# PLL.net
KiCad netlist of a schematic drawn in Altium Designer
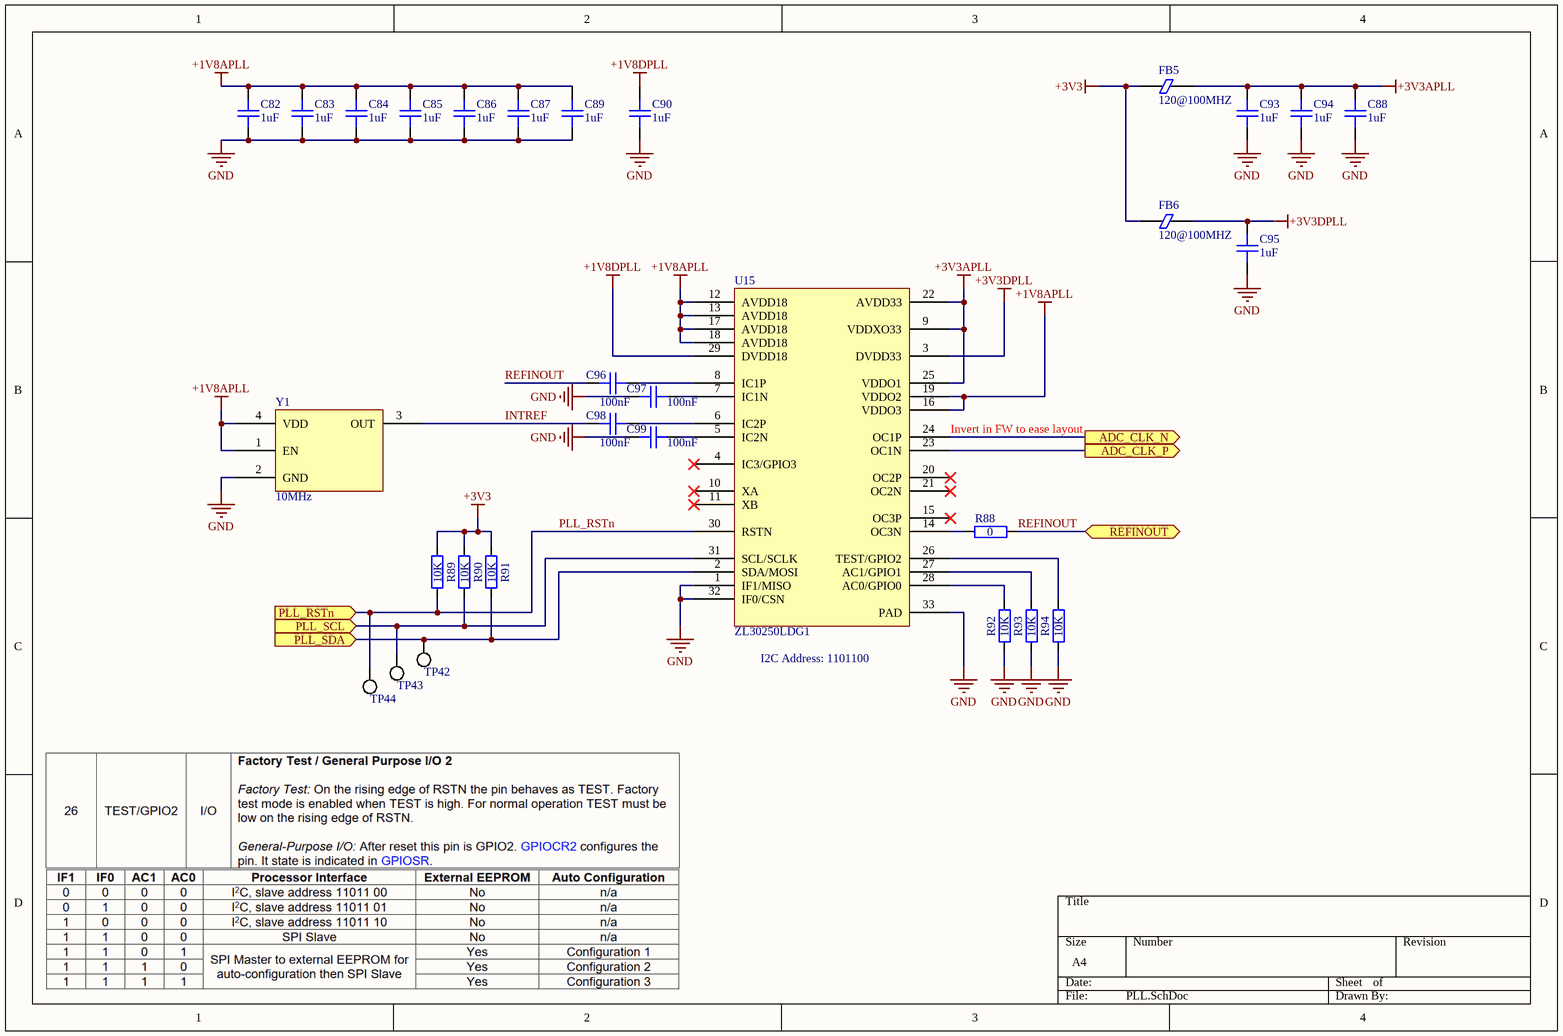
[diagram p0: PLL.SchDoc]

(export (version "E")
  (design (tool "Eeschema 10.0.6"))
  (components
    (comp (ref "C82")
      (value "1uF")
      (footprint "GEN_C_0402")
      (libsource (lib "DSO") (part "CAP 1uF 25V X5R 0402"))
    )
    (comp (ref "C83")
      (value "1uF")
      (footprint "GEN_C_0402")
      (libsource (lib "DSO") (part "CAP 1uF 25V X5R 0402"))
    )
    (comp (ref "C84")
      (value "1uF")
      (footprint "GEN_C_0402")
      (libsource (lib "DSO") (part "CAP 1uF 25V X5R 0402"))
    )
    (comp (ref "C85")
      (value "1uF")
      (footprint "GEN_C_0402")
      (libsource (lib "DSO") (part "CAP 1uF 25V X5R 0402"))
    )
    (comp (ref "C86")
      (value "1uF")
      (footprint "GEN_C_0402")
      (libsource (lib "DSO") (part "CAP 1uF 25V X5R 0402"))
    )
    (comp (ref "C87")
      (value "1uF")
      (footprint "GEN_C_0402")
      (libsource (lib "DSO") (part "CAP 1uF 25V X5R 0402"))
    )
    (comp (ref "C88")
      (value "1uF")
      (footprint "GEN_C_0402")
      (libsource (lib "DSO") (part "CAP 1uF 25V X5R 0402"))
    )
    (comp (ref "C89")
      (value "1uF")
      (footprint "GEN_C_0402")
      (libsource (lib "DSO") (part "CAP 1uF 25V X5R 0402"))
    )
    (comp (ref "C90")
      (value "1uF")
      (footprint "GEN_C_0402")
      (libsource (lib "DSO") (part "CAP 1uF 25V X5R 0402"))
    )
    (comp (ref "C93")
      (value "1uF")
      (footprint "GEN_C_0402")
      (libsource (lib "DSO") (part "CAP 1uF 25V X5R 0402"))
    )
    (comp (ref "C94")
      (value "1uF")
      (footprint "GEN_C_0402")
      (libsource (lib "DSO") (part "CAP 1uF 25V X5R 0402"))
    )
    (comp (ref "C95")
      (value "1uF")
      (footprint "GEN_C_0402")
      (libsource (lib "DSO") (part "CAP 1uF 25V X5R 0402"))
    )
    (comp (ref "C96")
      (value "100nF")
      (footprint "GEN_C_0402")
      (libsource (lib "DSO") (part "CAP 100nF 16V X7R 0402"))
    )
    (comp (ref "C97")
      (value "100nF")
      (footprint "GEN_C_0402")
      (libsource (lib "DSO") (part "CAP 100nF 16V X7R 0402"))
    )
    (comp (ref "C98")
      (value "100nF")
      (footprint "GEN_C_0402")
      (libsource (lib "DSO") (part "CAP 100nF 16V X7R 0402"))
    )
    (comp (ref "C99")
      (value "100nF")
      (footprint "GEN_C_0402")
      (libsource (lib "DSO") (part "CAP 100nF 16V X7R 0402"))
    )
    (comp (ref "FB5")
      (value "120@100MHZ")
      (footprint "GEN_R_0402")
      (libsource (lib "DSO") (part "FERRITE BEAD 120 OHM 0402"))
    )
    (comp (ref "FB6")
      (value "120@100MHZ")
      (footprint "GEN_R_0402")
      (libsource (lib "DSO") (part "FERRITE BEAD 120 OHM 0402"))
    )
    (comp (ref "R88")
      (value "0")
      (footprint "GEN_R_0402")
      (libsource (lib "DSO") (part "RES 0 OHM 1/16W 0402"))
    )
    (comp (ref "R89")
      (value "10K")
      (footprint "GEN_R_0402")
      (fields (field (name "TOLERANCE") "1%"))
      (libsource (lib "DSO") (part "RES 10K OHM 1% 1/10W 0402"))
    )
    (comp (ref "R90")
      (value "10K")
      (footprint "GEN_R_0402")
      (fields (field (name "TOLERANCE") "1%"))
      (libsource (lib "DSO") (part "RES 10K OHM 1% 1/10W 0402"))
    )
    (comp (ref "R91")
      (value "10K")
      (footprint "GEN_R_0402")
      (fields (field (name "TOLERANCE") "1%"))
      (libsource (lib "DSO") (part "RES 10K OHM 1% 1/10W 0402"))
    )
    (comp (ref "R92")
      (value "10K")
      (footprint "GEN_R_0402")
      (fields (field (name "TOLERANCE") "1%"))
      (libsource (lib "") (part "RES 10K OHM 1% 1/10W 0402_1"))
    )
    (comp (ref "R93")
      (value "10K")
      (footprint "GEN_R_0402")
      (fields (field (name "TOLERANCE") "1%"))
      (libsource (lib "") (part "RES 10K OHM 1% 1/10W 0402_1"))
    )
    (comp (ref "R94")
      (value "10K")
      (footprint "GEN_R_0402")
      (fields (field (name "TOLERANCE") "1%"))
      (libsource (lib "") (part "RES 10K OHM 1% 1/10W 0402_1"))
    )
    (comp (ref "TP42") (value "PCB") (footprint "GEN_TP_PCB") (libsource (lib "DSO") (part "TP PCB 1mm")))
    (comp (ref "TP43") (value "PCB") (footprint "GEN_TP_PCB") (libsource (lib "DSO") (part "TP PCB 1mm")))
    (comp (ref "TP44") (value "PCB") (footprint "GEN_TP_PCB") (libsource (lib "DSO") (part "TP PCB 1mm")))
    (comp (ref "U15")
      (value "ZL30250LDG1")
      (footprint "MC_QFN32_ZL30250")
      (libsource (lib "DSO") (part "IC CLK GEN ZL30250LDG1"))
    )
    (comp (ref "Y1")
      (value "10MHz")
      (footprint "ECS_TXO-3225")
      (libsource (lib "DSO") (part "OSC 10MHz ECS-TXO-3225MV"))
    )
  )
  (nets
    (net (code "1") (name "+1V8APLL") (class "Default")
      (node (ref "C82") (pin "1") (pinfunction "1_1") (pintype "passive"))
      (node (ref "C83") (pin "1") (pinfunction "1_1") (pintype "passive"))
      (node (ref "C84") (pin "1") (pinfunction "1_1") (pintype "passive"))
      (node (ref "C85") (pin "1") (pinfunction "1_1") (pintype "passive"))
      (node (ref "C86") (pin "1") (pinfunction "1_1") (pintype "passive"))
      (node (ref "C87") (pin "1") (pinfunction "1_1") (pintype "passive"))
      (node (ref "C89") (pin "1") (pinfunction "1_1") (pintype "passive"))
      (node (ref "U15") (pin "12") (pinfunction "AVDD18_12") (pintype "passive"))
      (node (ref "U15") (pin "13") (pinfunction "AVDD18_13") (pintype "passive"))
      (node (ref "U15") (pin "16") (pinfunction "VDDO3_16") (pintype "passive"))
      (node (ref "U15") (pin "17") (pinfunction "AVDD18_17") (pintype "passive"))
      (node (ref "U15") (pin "18") (pinfunction "AVDD18_18") (pintype "passive"))
      (node (ref "U15") (pin "19") (pinfunction "VDDO2_19") (pintype "passive"))
      (node (ref "Y1") (pin "1") (pinfunction "EN_1") (pintype "passive"))
      (node (ref "Y1") (pin "4") (pinfunction "VDD_4") (pintype "power_in"))
    )
    (net (code "2") (name "+1V8DPLL") (class "Default")
      (node (ref "C90") (pin "1") (pinfunction "1_1") (pintype "passive"))
      (node (ref "U15") (pin "29") (pinfunction "DVDD18_29") (pintype "passive"))
    )
    (net (code "3") (name "+3V3") (class "Default")
      (node (ref "FB5") (pin "1") (pinfunction "1_1") (pintype "passive"))
      (node (ref "FB6") (pin "1") (pinfunction "1_1") (pintype "passive"))
      (node (ref "R89") (pin "2") (pinfunction "2_2") (pintype "passive"))
      (node (ref "R90") (pin "2") (pinfunction "2_2") (pintype "passive"))
      (node (ref "R91") (pin "2") (pinfunction "2_2") (pintype "passive"))
    )
    (net (code "4") (name "+3V3APLL") (class "Default")
      (node (ref "C88") (pin "1") (pinfunction "1_1") (pintype "passive"))
      (node (ref "C93") (pin "1") (pinfunction "1_1") (pintype "passive"))
      (node (ref "C94") (pin "1") (pinfunction "1_1") (pintype "passive"))
      (node (ref "FB5") (pin "2") (pinfunction "2_2") (pintype "passive"))
      (node (ref "U15") (pin "22") (pinfunction "AVDD33_22") (pintype "passive"))
      (node (ref "U15") (pin "25") (pinfunction "VDDO1_25") (pintype "passive"))
      (node (ref "U15") (pin "9") (pinfunction "VDDXO33_9") (pintype "passive"))
    )
    (net (code "5") (name "+3V3DPLL") (class "Default")
      (node (ref "C95") (pin "1") (pinfunction "1_1") (pintype "passive"))
      (node (ref "FB6") (pin "2") (pinfunction "2_2") (pintype "passive"))
      (node (ref "U15") (pin "3") (pinfunction "DVDD33_3") (pintype "passive"))
    )
    (net (code "6") (name "/ADC_CLK_N") (class "Default")
      (node (ref "U15") (pin "24") (pinfunction "OC1P_24") (pintype "passive"))
    )
    (net (code "7") (name "/ADC_CLK_P") (class "Default")
      (node (ref "U15") (pin "23") (pinfunction "OC1N_23") (pintype "passive"))
    )
    (net (code "8") (name "/INTREF") (class "Default")
      (node (ref "C98") (pin "2") (pinfunction "2_2") (pintype "passive"))
      (node (ref "Y1") (pin "3") (pinfunction "OUT_3") (pintype "passive"))
    )
    (net (code "9") (name "/PLL_RSTn") (class "Default")
      (node (ref "R89") (pin "1") (pinfunction "1_1") (pintype "passive"))
      (node (ref "TP44") (pin "1") (pinfunction "1_1") (pintype "passive"))
      (node (ref "U15") (pin "30") (pinfunction "RSTN_30") (pintype "passive"))
    )
    (net (code "10") (name "/PLL_SCL") (class "Default")
      (node (ref "R90") (pin "1") (pinfunction "1_1") (pintype "passive"))
      (node (ref "TP43") (pin "1") (pinfunction "1_1") (pintype "passive"))
      (node (ref "U15") (pin "31") (pinfunction "SCL/SCLK_31") (pintype "passive"))
    )
    (net (code "11") (name "/PLL_SDA") (class "Default")
      (node (ref "R91") (pin "1") (pinfunction "1_1") (pintype "passive"))
      (node (ref "TP42") (pin "1") (pinfunction "1_1") (pintype "passive"))
      (node (ref "U15") (pin "2") (pinfunction "SDA/MOSI_2") (pintype "passive"))
    )
    (net (code "12") (name "/REFINOUT") (class "Default")
      (node (ref "C96") (pin "2") (pinfunction "2_2") (pintype "passive"))
      (node (ref "R88") (pin "2") (pinfunction "2_2") (pintype "passive"))
    )
    (net (code "13") (name "GND") (class "Default")
      (node (ref "C82") (pin "2") (pinfunction "2_2") (pintype "passive"))
      (node (ref "C83") (pin "2") (pinfunction "2_2") (pintype "passive"))
      (node (ref "C84") (pin "2") (pinfunction "2_2") (pintype "passive"))
      (node (ref "C85") (pin "2") (pinfunction "2_2") (pintype "passive"))
      (node (ref "C86") (pin "2") (pinfunction "2_2") (pintype "passive"))
      (node (ref "C87") (pin "2") (pinfunction "2_2") (pintype "passive"))
      (node (ref "C88") (pin "2") (pinfunction "2_2") (pintype "passive"))
      (node (ref "C89") (pin "2") (pinfunction "2_2") (pintype "passive"))
      (node (ref "C90") (pin "2") (pinfunction "2_2") (pintype "passive"))
      (node (ref "C93") (pin "2") (pinfunction "2_2") (pintype "passive"))
      (node (ref "C94") (pin "2") (pinfunction "2_2") (pintype "passive"))
      (node (ref "C95") (pin "2") (pinfunction "2_2") (pintype "passive"))
      (node (ref "C97") (pin "2") (pinfunction "2_2") (pintype "passive"))
      (node (ref "C99") (pin "2") (pinfunction "2_2") (pintype "passive"))
      (node (ref "R92") (pin "1") (pinfunction "1_1") (pintype "passive"))
      (node (ref "R93") (pin "1") (pinfunction "1_1") (pintype "passive"))
      (node (ref "R94") (pin "1") (pinfunction "1_1") (pintype "passive"))
      (node (ref "U15") (pin "1") (pinfunction "IF1/MISO_1") (pintype "passive"))
      (node (ref "U15") (pin "32") (pinfunction "IF0/CSN_32") (pintype "passive"))
      (node (ref "U15") (pin "33") (pinfunction "PAD_33") (pintype "passive"))
      (node (ref "Y1") (pin "2") (pinfunction "GND_2") (pintype "power_in"))
    )
    (net (code "14") (name "Net-(U15-AC0{slash}GPIO0)") (class "Default")
      (node (ref "R92") (pin "2") (pinfunction "2_2") (pintype "passive"))
      (node (ref "U15") (pin "28") (pinfunction "AC0/GPIO0_28") (pintype "passive"))
    )
    (net (code "15") (name "Net-(U15-AC1{slash}GPIO1)") (class "Default")
      (node (ref "R93") (pin "2") (pinfunction "2_2") (pintype "passive"))
      (node (ref "U15") (pin "27") (pinfunction "AC1/GPIO1_27") (pintype "passive"))
    )
    (net (code "16") (name "Net-(U15-IC1N)") (class "Default")
      (node (ref "C97") (pin "1") (pinfunction "1_1") (pintype "passive"))
      (node (ref "U15") (pin "7") (pinfunction "IC1N_7") (pintype "passive"))
    )
    (net (code "17") (name "Net-(U15-IC1P)") (class "Default")
      (node (ref "C96") (pin "1") (pinfunction "1_1") (pintype "passive"))
      (node (ref "U15") (pin "8") (pinfunction "IC1P_8") (pintype "passive"))
    )
    (net (code "18") (name "Net-(U15-IC2N)") (class "Default")
      (node (ref "C99") (pin "1") (pinfunction "1_1") (pintype "passive"))
      (node (ref "U15") (pin "5") (pinfunction "IC2N_5") (pintype "passive"))
    )
    (net (code "19") (name "Net-(U15-IC2P)") (class "Default")
      (node (ref "C98") (pin "1") (pinfunction "1_1") (pintype "passive"))
      (node (ref "U15") (pin "6") (pinfunction "IC2P_6") (pintype "passive"))
    )
    (net (code "20") (name "Net-(U15-OC3N)") (class "Default")
      (node (ref "R88") (pin "1") (pinfunction "1_1") (pintype "passive"))
      (node (ref "U15") (pin "14") (pinfunction "OC3N_14") (pintype "passive"))
    )
    (net (code "21") (name "Net-(U15-TEST{slash}GPIO2)") (class "Default")
      (node (ref "R94") (pin "2") (pinfunction "2_2") (pintype "passive"))
      (node (ref "U15") (pin "26") (pinfunction "TEST/GPIO2_26") (pintype "passive"))
    )
    (net (code "22") (name "unconnected-(U15-IC3{slash}GPIO3-Pad4)") (class "Default")
      (node (ref "U15") (pin "4") (pinfunction "IC3/GPIO3_4") (pintype "passive+no_connect"))
    )
    (net (code "23") (name "unconnected-(U15-OC2N-Pad21)") (class "Default")
      (node (ref "U15") (pin "21") (pinfunction "OC2N_21") (pintype "passive+no_connect"))
    )
    (net (code "24") (name "unconnected-(U15-OC2P-Pad20)") (class "Default")
      (node (ref "U15") (pin "20") (pinfunction "OC2P_20") (pintype "passive+no_connect"))
    )
    (net (code "25") (name "unconnected-(U15-OC3P-Pad15)") (class "Default")
      (node (ref "U15") (pin "15") (pinfunction "OC3P_15") (pintype "passive+no_connect"))
    )
    (net (code "26") (name "unconnected-(U15-XA-Pad10)") (class "Default")
      (node (ref "U15") (pin "10") (pinfunction "XA_10") (pintype "passive+no_connect"))
    )
    (net (code "27") (name "unconnected-(U15-XB-Pad11)") (class "Default")
      (node (ref "U15") (pin "11") (pinfunction "XB_11") (pintype "passive+no_connect"))
    )
  )
)
